# Sheet1.net
KiCad netlist of a schematic drawn in Altium Designer
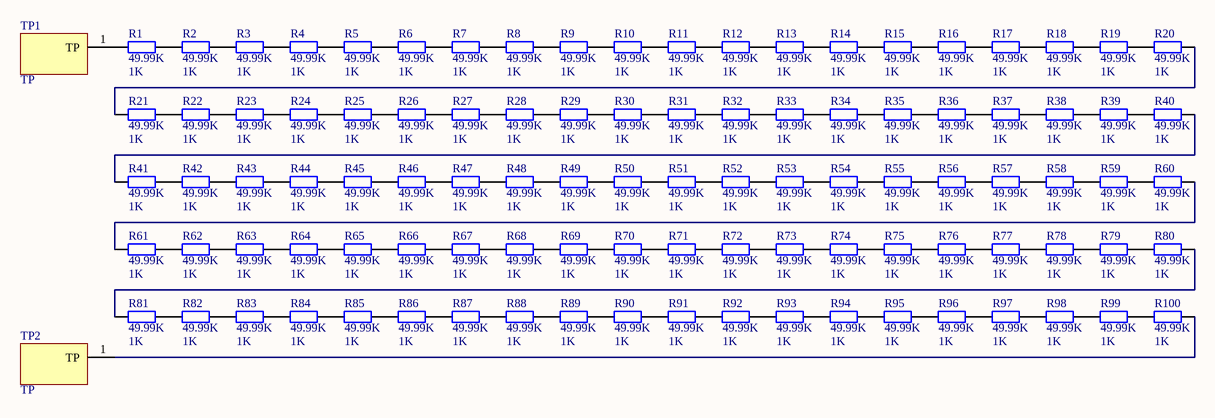
[diagram p0: Sheet1.SchDoc]

(export (version "E")
  (design (tool "Eeschema 10.0.6"))
  (components
    (comp (ref "R1")
      (value "49.99K")
      (footprint "AXIAL-0.4")
      (description "Resistor")
      (fields (field (name "ALTIUM_VALUE") "1K") (field (name "PUBLISHER") "Altium Limited"))
      (libsource (lib "Miscellaneous Devices") (part "Res2"))
    )
    (comp (ref "R2")
      (value "49.99K")
      (footprint "AXIAL-0.4")
      (description "Resistor")
      (fields (field (name "ALTIUM_VALUE") "1K") (field (name "PUBLISHER") "Altium Limited"))
      (libsource (lib "Miscellaneous Devices") (part "Res2"))
    )
    (comp (ref "R3")
      (value "49.99K")
      (footprint "AXIAL-0.4")
      (description "Resistor")
      (fields (field (name "ALTIUM_VALUE") "1K") (field (name "PUBLISHER") "Altium Limited"))
      (libsource (lib "Miscellaneous Devices") (part "Res2"))
    )
    (comp (ref "R4")
      (value "49.99K")
      (footprint "AXIAL-0.4")
      (description "Resistor")
      (fields (field (name "ALTIUM_VALUE") "1K") (field (name "PUBLISHER") "Altium Limited"))
      (libsource (lib "Miscellaneous Devices") (part "Res2"))
    )
    (comp (ref "R5")
      (value "49.99K")
      (footprint "AXIAL-0.4")
      (description "Resistor")
      (fields (field (name "ALTIUM_VALUE") "1K") (field (name "PUBLISHER") "Altium Limited"))
      (libsource (lib "Miscellaneous Devices") (part "Res2"))
    )
    (comp (ref "R6")
      (value "49.99K")
      (footprint "AXIAL-0.4")
      (description "Resistor")
      (fields (field (name "ALTIUM_VALUE") "1K") (field (name "PUBLISHER") "Altium Limited"))
      (libsource (lib "Miscellaneous Devices") (part "Res2"))
    )
    (comp (ref "R7")
      (value "49.99K")
      (footprint "AXIAL-0.4")
      (description "Resistor")
      (fields (field (name "ALTIUM_VALUE") "1K") (field (name "PUBLISHER") "Altium Limited"))
      (libsource (lib "Miscellaneous Devices") (part "Res2"))
    )
    (comp (ref "R8")
      (value "49.99K")
      (footprint "AXIAL-0.4")
      (description "Resistor")
      (fields (field (name "ALTIUM_VALUE") "1K") (field (name "PUBLISHER") "Altium Limited"))
      (libsource (lib "Miscellaneous Devices") (part "Res2"))
    )
    (comp (ref "R9")
      (value "49.99K")
      (footprint "AXIAL-0.4")
      (description "Resistor")
      (fields (field (name "ALTIUM_VALUE") "1K") (field (name "PUBLISHER") "Altium Limited"))
      (libsource (lib "Miscellaneous Devices") (part "Res2"))
    )
    (comp (ref "R10")
      (value "49.99K")
      (footprint "AXIAL-0.4")
      (description "Resistor")
      (fields (field (name "ALTIUM_VALUE") "1K") (field (name "PUBLISHER") "Altium Limited"))
      (libsource (lib "Miscellaneous Devices") (part "Res2"))
    )
    (comp (ref "R11")
      (value "49.99K")
      (footprint "AXIAL-0.4")
      (description "Resistor")
      (fields (field (name "ALTIUM_VALUE") "1K") (field (name "PUBLISHER") "Altium Limited"))
      (libsource (lib "Miscellaneous Devices") (part "Res2"))
    )
    (comp (ref "R12")
      (value "49.99K")
      (footprint "AXIAL-0.4")
      (description "Resistor")
      (fields (field (name "ALTIUM_VALUE") "1K") (field (name "PUBLISHER") "Altium Limited"))
      (libsource (lib "Miscellaneous Devices") (part "Res2"))
    )
    (comp (ref "R13")
      (value "49.99K")
      (footprint "AXIAL-0.4")
      (description "Resistor")
      (fields (field (name "ALTIUM_VALUE") "1K") (field (name "PUBLISHER") "Altium Limited"))
      (libsource (lib "Miscellaneous Devices") (part "Res2"))
    )
    (comp (ref "R14")
      (value "49.99K")
      (footprint "AXIAL-0.4")
      (description "Resistor")
      (fields (field (name "ALTIUM_VALUE") "1K") (field (name "PUBLISHER") "Altium Limited"))
      (libsource (lib "Miscellaneous Devices") (part "Res2"))
    )
    (comp (ref "R15")
      (value "49.99K")
      (footprint "AXIAL-0.4")
      (description "Resistor")
      (fields (field (name "ALTIUM_VALUE") "1K") (field (name "PUBLISHER") "Altium Limited"))
      (libsource (lib "Miscellaneous Devices") (part "Res2"))
    )
    (comp (ref "R16")
      (value "49.99K")
      (footprint "AXIAL-0.4")
      (description "Resistor")
      (fields (field (name "ALTIUM_VALUE") "1K") (field (name "PUBLISHER") "Altium Limited"))
      (libsource (lib "Miscellaneous Devices") (part "Res2"))
    )
    (comp (ref "R17")
      (value "49.99K")
      (footprint "AXIAL-0.4")
      (description "Resistor")
      (fields (field (name "ALTIUM_VALUE") "1K") (field (name "PUBLISHER") "Altium Limited"))
      (libsource (lib "Miscellaneous Devices") (part "Res2"))
    )
    (comp (ref "R18")
      (value "49.99K")
      (footprint "AXIAL-0.4")
      (description "Resistor")
      (fields (field (name "ALTIUM_VALUE") "1K") (field (name "PUBLISHER") "Altium Limited"))
      (libsource (lib "Miscellaneous Devices") (part "Res2"))
    )
    (comp (ref "R19")
      (value "49.99K")
      (footprint "AXIAL-0.4")
      (description "Resistor")
      (fields (field (name "ALTIUM_VALUE") "1K") (field (name "PUBLISHER") "Altium Limited"))
      (libsource (lib "Miscellaneous Devices") (part "Res2"))
    )
    (comp (ref "R20")
      (value "49.99K")
      (footprint "AXIAL-0.4")
      (description "Resistor")
      (fields (field (name "ALTIUM_VALUE") "1K") (field (name "PUBLISHER") "Altium Limited"))
      (libsource (lib "Miscellaneous Devices") (part "Res2"))
    )
    (comp (ref "R21")
      (value "49.99K")
      (footprint "AXIAL-0.4")
      (description "Resistor")
      (fields (field (name "ALTIUM_VALUE") "1K") (field (name "PUBLISHER") "Altium Limited"))
      (libsource (lib "Miscellaneous Devices") (part "Res2"))
    )
    (comp (ref "R22")
      (value "49.99K")
      (footprint "AXIAL-0.4")
      (description "Resistor")
      (fields (field (name "ALTIUM_VALUE") "1K") (field (name "PUBLISHER") "Altium Limited"))
      (libsource (lib "Miscellaneous Devices") (part "Res2"))
    )
    (comp (ref "R23")
      (value "49.99K")
      (footprint "AXIAL-0.4")
      (description "Resistor")
      (fields (field (name "ALTIUM_VALUE") "1K") (field (name "PUBLISHER") "Altium Limited"))
      (libsource (lib "Miscellaneous Devices") (part "Res2"))
    )
    (comp (ref "R24")
      (value "49.99K")
      (footprint "AXIAL-0.4")
      (description "Resistor")
      (fields (field (name "ALTIUM_VALUE") "1K") (field (name "PUBLISHER") "Altium Limited"))
      (libsource (lib "Miscellaneous Devices") (part "Res2"))
    )
    (comp (ref "R25")
      (value "49.99K")
      (footprint "AXIAL-0.4")
      (description "Resistor")
      (fields (field (name "ALTIUM_VALUE") "1K") (field (name "PUBLISHER") "Altium Limited"))
      (libsource (lib "Miscellaneous Devices") (part "Res2"))
    )
    (comp (ref "R26")
      (value "49.99K")
      (footprint "AXIAL-0.4")
      (description "Resistor")
      (fields (field (name "ALTIUM_VALUE") "1K") (field (name "PUBLISHER") "Altium Limited"))
      (libsource (lib "Miscellaneous Devices") (part "Res2"))
    )
    (comp (ref "R27")
      (value "49.99K")
      (footprint "AXIAL-0.4")
      (description "Resistor")
      (fields (field (name "ALTIUM_VALUE") "1K") (field (name "PUBLISHER") "Altium Limited"))
      (libsource (lib "Miscellaneous Devices") (part "Res2"))
    )
    (comp (ref "R28")
      (value "49.99K")
      (footprint "AXIAL-0.4")
      (description "Resistor")
      (fields (field (name "ALTIUM_VALUE") "1K") (field (name "PUBLISHER") "Altium Limited"))
      (libsource (lib "Miscellaneous Devices") (part "Res2"))
    )
    (comp (ref "R29")
      (value "49.99K")
      (footprint "AXIAL-0.4")
      (description "Resistor")
      (fields (field (name "ALTIUM_VALUE") "1K") (field (name "PUBLISHER") "Altium Limited"))
      (libsource (lib "Miscellaneous Devices") (part "Res2"))
    )
    (comp (ref "R30")
      (value "49.99K")
      (footprint "AXIAL-0.4")
      (description "Resistor")
      (fields (field (name "ALTIUM_VALUE") "1K") (field (name "PUBLISHER") "Altium Limited"))
      (libsource (lib "Miscellaneous Devices") (part "Res2"))
    )
    (comp (ref "R31")
      (value "49.99K")
      (footprint "AXIAL-0.4")
      (description "Resistor")
      (fields (field (name "ALTIUM_VALUE") "1K") (field (name "PUBLISHER") "Altium Limited"))
      (libsource (lib "Miscellaneous Devices") (part "Res2"))
    )
    (comp (ref "R32")
      (value "49.99K")
      (footprint "AXIAL-0.4")
      (description "Resistor")
      (fields (field (name "ALTIUM_VALUE") "1K") (field (name "PUBLISHER") "Altium Limited"))
      (libsource (lib "Miscellaneous Devices") (part "Res2"))
    )
    (comp (ref "R33")
      (value "49.99K")
      (footprint "AXIAL-0.4")
      (description "Resistor")
      (fields (field (name "ALTIUM_VALUE") "1K") (field (name "PUBLISHER") "Altium Limited"))
      (libsource (lib "Miscellaneous Devices") (part "Res2"))
    )
    (comp (ref "R34")
      (value "49.99K")
      (footprint "AXIAL-0.4")
      (description "Resistor")
      (fields (field (name "ALTIUM_VALUE") "1K") (field (name "PUBLISHER") "Altium Limited"))
      (libsource (lib "Miscellaneous Devices") (part "Res2"))
    )
    (comp (ref "R35")
      (value "49.99K")
      (footprint "AXIAL-0.4")
      (description "Resistor")
      (fields (field (name "ALTIUM_VALUE") "1K") (field (name "PUBLISHER") "Altium Limited"))
      (libsource (lib "Miscellaneous Devices") (part "Res2"))
    )
    (comp (ref "R36")
      (value "49.99K")
      (footprint "AXIAL-0.4")
      (description "Resistor")
      (fields (field (name "ALTIUM_VALUE") "1K") (field (name "PUBLISHER") "Altium Limited"))
      (libsource (lib "Miscellaneous Devices") (part "Res2"))
    )
    (comp (ref "R37")
      (value "49.99K")
      (footprint "AXIAL-0.4")
      (description "Resistor")
      (fields (field (name "ALTIUM_VALUE") "1K") (field (name "PUBLISHER") "Altium Limited"))
      (libsource (lib "Miscellaneous Devices") (part "Res2"))
    )
    (comp (ref "R38")
      (value "49.99K")
      (footprint "AXIAL-0.4")
      (description "Resistor")
      (fields (field (name "ALTIUM_VALUE") "1K") (field (name "PUBLISHER") "Altium Limited"))
      (libsource (lib "Miscellaneous Devices") (part "Res2"))
    )
    (comp (ref "R39")
      (value "49.99K")
      (footprint "AXIAL-0.4")
      (description "Resistor")
      (fields (field (name "ALTIUM_VALUE") "1K") (field (name "PUBLISHER") "Altium Limited"))
      (libsource (lib "Miscellaneous Devices") (part "Res2"))
    )
    (comp (ref "R40")
      (value "49.99K")
      (footprint "AXIAL-0.4")
      (description "Resistor")
      (fields (field (name "ALTIUM_VALUE") "1K") (field (name "PUBLISHER") "Altium Limited"))
      (libsource (lib "Miscellaneous Devices") (part "Res2"))
    )
    (comp (ref "R41")
      (value "49.99K")
      (footprint "AXIAL-0.4")
      (description "Resistor")
      (fields (field (name "ALTIUM_VALUE") "1K") (field (name "PUBLISHER") "Altium Limited"))
      (libsource (lib "Miscellaneous Devices") (part "Res2"))
    )
    (comp (ref "R42")
      (value "49.99K")
      (footprint "AXIAL-0.4")
      (description "Resistor")
      (fields (field (name "ALTIUM_VALUE") "1K") (field (name "PUBLISHER") "Altium Limited"))
      (libsource (lib "Miscellaneous Devices") (part "Res2"))
    )
    (comp (ref "R43")
      (value "49.99K")
      (footprint "AXIAL-0.4")
      (description "Resistor")
      (fields (field (name "ALTIUM_VALUE") "1K") (field (name "PUBLISHER") "Altium Limited"))
      (libsource (lib "Miscellaneous Devices") (part "Res2"))
    )
    (comp (ref "R44")
      (value "49.99K")
      (footprint "AXIAL-0.4")
      (description "Resistor")
      (fields (field (name "ALTIUM_VALUE") "1K") (field (name "PUBLISHER") "Altium Limited"))
      (libsource (lib "Miscellaneous Devices") (part "Res2"))
    )
    (comp (ref "R45")
      (value "49.99K")
      (footprint "AXIAL-0.4")
      (description "Resistor")
      (fields (field (name "ALTIUM_VALUE") "1K") (field (name "PUBLISHER") "Altium Limited"))
      (libsource (lib "Miscellaneous Devices") (part "Res2"))
    )
    (comp (ref "R46")
      (value "49.99K")
      (footprint "AXIAL-0.4")
      (description "Resistor")
      (fields (field (name "ALTIUM_VALUE") "1K") (field (name "PUBLISHER") "Altium Limited"))
      (libsource (lib "Miscellaneous Devices") (part "Res2"))
    )
    (comp (ref "R47")
      (value "49.99K")
      (footprint "AXIAL-0.4")
      (description "Resistor")
      (fields (field (name "ALTIUM_VALUE") "1K") (field (name "PUBLISHER") "Altium Limited"))
      (libsource (lib "Miscellaneous Devices") (part "Res2"))
    )
    (comp (ref "R48")
      (value "49.99K")
      (footprint "AXIAL-0.4")
      (description "Resistor")
      (fields (field (name "ALTIUM_VALUE") "1K") (field (name "PUBLISHER") "Altium Limited"))
      (libsource (lib "Miscellaneous Devices") (part "Res2"))
    )
    (comp (ref "R49")
      (value "49.99K")
      (footprint "AXIAL-0.4")
      (description "Resistor")
      (fields (field (name "ALTIUM_VALUE") "1K") (field (name "PUBLISHER") "Altium Limited"))
      (libsource (lib "Miscellaneous Devices") (part "Res2"))
    )
    (comp (ref "R50")
      (value "49.99K")
      (footprint "AXIAL-0.4")
      (description "Resistor")
      (fields (field (name "ALTIUM_VALUE") "1K") (field (name "PUBLISHER") "Altium Limited"))
      (libsource (lib "Miscellaneous Devices") (part "Res2"))
    )
    (comp (ref "R51")
      (value "49.99K")
      (footprint "AXIAL-0.4")
      (description "Resistor")
      (fields (field (name "ALTIUM_VALUE") "1K") (field (name "PUBLISHER") "Altium Limited"))
      (libsource (lib "Miscellaneous Devices") (part "Res2"))
    )
    (comp (ref "R52")
      (value "49.99K")
      (footprint "AXIAL-0.4")
      (description "Resistor")
      (fields (field (name "ALTIUM_VALUE") "1K") (field (name "PUBLISHER") "Altium Limited"))
      (libsource (lib "Miscellaneous Devices") (part "Res2"))
    )
    (comp (ref "R53")
      (value "49.99K")
      (footprint "AXIAL-0.4")
      (description "Resistor")
      (fields (field (name "ALTIUM_VALUE") "1K") (field (name "PUBLISHER") "Altium Limited"))
      (libsource (lib "Miscellaneous Devices") (part "Res2"))
    )
    (comp (ref "R54")
      (value "49.99K")
      (footprint "AXIAL-0.4")
      (description "Resistor")
      (fields (field (name "ALTIUM_VALUE") "1K") (field (name "PUBLISHER") "Altium Limited"))
      (libsource (lib "Miscellaneous Devices") (part "Res2"))
    )
    (comp (ref "R55")
      (value "49.99K")
      (footprint "AXIAL-0.4")
      (description "Resistor")
      (fields (field (name "ALTIUM_VALUE") "1K") (field (name "PUBLISHER") "Altium Limited"))
      (libsource (lib "Miscellaneous Devices") (part "Res2"))
    )
    (comp (ref "R56")
      (value "49.99K")
      (footprint "AXIAL-0.4")
      (description "Resistor")
      (fields (field (name "ALTIUM_VALUE") "1K") (field (name "PUBLISHER") "Altium Limited"))
      (libsource (lib "Miscellaneous Devices") (part "Res2"))
    )
    (comp (ref "R57")
      (value "49.99K")
      (footprint "AXIAL-0.4")
      (description "Resistor")
      (fields (field (name "ALTIUM_VALUE") "1K") (field (name "PUBLISHER") "Altium Limited"))
      (libsource (lib "Miscellaneous Devices") (part "Res2"))
    )
    (comp (ref "R58")
      (value "49.99K")
      (footprint "AXIAL-0.4")
      (description "Resistor")
      (fields (field (name "ALTIUM_VALUE") "1K") (field (name "PUBLISHER") "Altium Limited"))
      (libsource (lib "Miscellaneous Devices") (part "Res2"))
    )
    (comp (ref "R59")
      (value "49.99K")
      (footprint "AXIAL-0.4")
      (description "Resistor")
      (fields (field (name "ALTIUM_VALUE") "1K") (field (name "PUBLISHER") "Altium Limited"))
      (libsource (lib "Miscellaneous Devices") (part "Res2"))
    )
    (comp (ref "R60")
      (value "49.99K")
      (footprint "AXIAL-0.4")
      (description "Resistor")
      (fields (field (name "ALTIUM_VALUE") "1K") (field (name "PUBLISHER") "Altium Limited"))
      (libsource (lib "Miscellaneous Devices") (part "Res2"))
    )
    (comp (ref "R61")
      (value "49.99K")
      (footprint "AXIAL-0.4")
      (description "Resistor")
      (fields (field (name "ALTIUM_VALUE") "1K") (field (name "PUBLISHER") "Altium Limited"))
      (libsource (lib "Miscellaneous Devices") (part "Res2"))
    )
    (comp (ref "R62")
      (value "49.99K")
      (footprint "AXIAL-0.4")
      (description "Resistor")
      (fields (field (name "ALTIUM_VALUE") "1K") (field (name "PUBLISHER") "Altium Limited"))
      (libsource (lib "Miscellaneous Devices") (part "Res2"))
    )
    (comp (ref "R63")
      (value "49.99K")
      (footprint "AXIAL-0.4")
      (description "Resistor")
      (fields (field (name "ALTIUM_VALUE") "1K") (field (name "PUBLISHER") "Altium Limited"))
      (libsource (lib "Miscellaneous Devices") (part "Res2"))
    )
    (comp (ref "R64")
      (value "49.99K")
      (footprint "AXIAL-0.4")
      (description "Resistor")
      (fields (field (name "ALTIUM_VALUE") "1K") (field (name "PUBLISHER") "Altium Limited"))
      (libsource (lib "Miscellaneous Devices") (part "Res2"))
    )
    (comp (ref "R65")
      (value "49.99K")
      (footprint "AXIAL-0.4")
      (description "Resistor")
      (fields (field (name "ALTIUM_VALUE") "1K") (field (name "PUBLISHER") "Altium Limited"))
      (libsource (lib "Miscellaneous Devices") (part "Res2"))
    )
    (comp (ref "R66")
      (value "49.99K")
      (footprint "AXIAL-0.4")
      (description "Resistor")
      (fields (field (name "ALTIUM_VALUE") "1K") (field (name "PUBLISHER") "Altium Limited"))
      (libsource (lib "Miscellaneous Devices") (part "Res2"))
    )
    (comp (ref "R67")
      (value "49.99K")
      (footprint "AXIAL-0.4")
      (description "Resistor")
      (fields (field (name "ALTIUM_VALUE") "1K") (field (name "PUBLISHER") "Altium Limited"))
      (libsource (lib "Miscellaneous Devices") (part "Res2"))
    )
    (comp (ref "R68")
      (value "49.99K")
      (footprint "AXIAL-0.4")
      (description "Resistor")
      (fields (field (name "ALTIUM_VALUE") "1K") (field (name "PUBLISHER") "Altium Limited"))
      (libsource (lib "Miscellaneous Devices") (part "Res2"))
    )
    (comp (ref "R69")
      (value "49.99K")
      (footprint "AXIAL-0.4")
      (description "Resistor")
      (fields (field (name "ALTIUM_VALUE") "1K") (field (name "PUBLISHER") "Altium Limited"))
      (libsource (lib "Miscellaneous Devices") (part "Res2"))
    )
    (comp (ref "R70")
      (value "49.99K")
      (footprint "AXIAL-0.4")
      (description "Resistor")
      (fields (field (name "ALTIUM_VALUE") "1K") (field (name "PUBLISHER") "Altium Limited"))
      (libsource (lib "Miscellaneous Devices") (part "Res2"))
    )
    (comp (ref "R71")
      (value "49.99K")
      (footprint "AXIAL-0.4")
      (description "Resistor")
      (fields (field (name "ALTIUM_VALUE") "1K") (field (name "PUBLISHER") "Altium Limited"))
      (libsource (lib "Miscellaneous Devices") (part "Res2"))
    )
    (comp (ref "R72")
      (value "49.99K")
      (footprint "AXIAL-0.4")
      (description "Resistor")
      (fields (field (name "ALTIUM_VALUE") "1K") (field (name "PUBLISHER") "Altium Limited"))
      (libsource (lib "Miscellaneous Devices") (part "Res2"))
    )
    (comp (ref "R73")
      (value "49.99K")
      (footprint "AXIAL-0.4")
      (description "Resistor")
      (fields (field (name "ALTIUM_VALUE") "1K") (field (name "PUBLISHER") "Altium Limited"))
      (libsource (lib "Miscellaneous Devices") (part "Res2"))
    )
    (comp (ref "R74")
      (value "49.99K")
      (footprint "AXIAL-0.4")
      (description "Resistor")
      (fields (field (name "ALTIUM_VALUE") "1K") (field (name "PUBLISHER") "Altium Limited"))
      (libsource (lib "Miscellaneous Devices") (part "Res2"))
    )
    (comp (ref "R75")
      (value "49.99K")
      (footprint "AXIAL-0.4")
      (description "Resistor")
      (fields (field (name "ALTIUM_VALUE") "1K") (field (name "PUBLISHER") "Altium Limited"))
      (libsource (lib "Miscellaneous Devices") (part "Res2"))
    )
    (comp (ref "R76")
      (value "49.99K")
      (footprint "AXIAL-0.4")
      (description "Resistor")
      (fields (field (name "ALTIUM_VALUE") "1K") (field (name "PUBLISHER") "Altium Limited"))
      (libsource (lib "Miscellaneous Devices") (part "Res2"))
    )
    (comp (ref "R77")
      (value "49.99K")
      (footprint "AXIAL-0.4")
      (description "Resistor")
      (fields (field (name "ALTIUM_VALUE") "1K") (field (name "PUBLISHER") "Altium Limited"))
      (libsource (lib "Miscellaneous Devices") (part "Res2"))
    )
    (comp (ref "R78")
      (value "49.99K")
      (footprint "AXIAL-0.4")
      (description "Resistor")
      (fields (field (name "ALTIUM_VALUE") "1K") (field (name "PUBLISHER") "Altium Limited"))
      (libsource (lib "Miscellaneous Devices") (part "Res2"))
    )
    (comp (ref "R79")
      (value "49.99K")
      (footprint "AXIAL-0.4")
      (description "Resistor")
      (fields (field (name "ALTIUM_VALUE") "1K") (field (name "PUBLISHER") "Altium Limited"))
      (libsource (lib "Miscellaneous Devices") (part "Res2"))
    )
    (comp (ref "R80")
      (value "49.99K")
      (footprint "AXIAL-0.4")
      (description "Resistor")
      (fields (field (name "ALTIUM_VALUE") "1K") (field (name "PUBLISHER") "Altium Limited"))
      (libsource (lib "Miscellaneous Devices") (part "Res2"))
    )
    (comp (ref "R81")
      (value "49.99K")
      (footprint "AXIAL-0.4")
      (description "Resistor")
      (fields (field (name "ALTIUM_VALUE") "1K") (field (name "PUBLISHER") "Altium Limited"))
      (libsource (lib "Miscellaneous Devices") (part "Res2"))
    )
    (comp (ref "R82")
      (value "49.99K")
      (footprint "AXIAL-0.4")
      (description "Resistor")
      (fields (field (name "ALTIUM_VALUE") "1K") (field (name "PUBLISHER") "Altium Limited"))
      (libsource (lib "Miscellaneous Devices") (part "Res2"))
    )
    (comp (ref "R83")
      (value "49.99K")
      (footprint "AXIAL-0.4")
      (description "Resistor")
      (fields (field (name "ALTIUM_VALUE") "1K") (field (name "PUBLISHER") "Altium Limited"))
      (libsource (lib "Miscellaneous Devices") (part "Res2"))
    )
    (comp (ref "R84")
      (value "49.99K")
      (footprint "AXIAL-0.4")
      (description "Resistor")
      (fields (field (name "ALTIUM_VALUE") "1K") (field (name "PUBLISHER") "Altium Limited"))
      (libsource (lib "Miscellaneous Devices") (part "Res2"))
    )
    (comp (ref "R85")
      (value "49.99K")
      (footprint "AXIAL-0.4")
      (description "Resistor")
      (fields (field (name "ALTIUM_VALUE") "1K") (field (name "PUBLISHER") "Altium Limited"))
      (libsource (lib "Miscellaneous Devices") (part "Res2"))
    )
    (comp (ref "R86")
      (value "49.99K")
      (footprint "AXIAL-0.4")
      (description "Resistor")
      (fields (field (name "ALTIUM_VALUE") "1K") (field (name "PUBLISHER") "Altium Limited"))
      (libsource (lib "Miscellaneous Devices") (part "Res2"))
    )
    (comp (ref "R87")
      (value "49.99K")
      (footprint "AXIAL-0.4")
      (description "Resistor")
      (fields (field (name "ALTIUM_VALUE") "1K") (field (name "PUBLISHER") "Altium Limited"))
      (libsource (lib "Miscellaneous Devices") (part "Res2"))
    )
    (comp (ref "R88")
      (value "49.99K")
      (footprint "AXIAL-0.4")
      (description "Resistor")
      (fields (field (name "ALTIUM_VALUE") "1K") (field (name "PUBLISHER") "Altium Limited"))
      (libsource (lib "Miscellaneous Devices") (part "Res2"))
    )
    (comp (ref "R89")
      (value "49.99K")
      (footprint "AXIAL-0.4")
      (description "Resistor")
      (fields (field (name "ALTIUM_VALUE") "1K") (field (name "PUBLISHER") "Altium Limited"))
      (libsource (lib "Miscellaneous Devices") (part "Res2"))
    )
    (comp (ref "R90")
      (value "49.99K")
      (footprint "AXIAL-0.4")
      (description "Resistor")
      (fields (field (name "ALTIUM_VALUE") "1K") (field (name "PUBLISHER") "Altium Limited"))
      (libsource (lib "Miscellaneous Devices") (part "Res2"))
    )
    (comp (ref "R91")
      (value "49.99K")
      (footprint "AXIAL-0.4")
      (description "Resistor")
      (fields (field (name "ALTIUM_VALUE") "1K") (field (name "PUBLISHER") "Altium Limited"))
      (libsource (lib "Miscellaneous Devices") (part "Res2"))
    )
    (comp (ref "R92")
      (value "49.99K")
      (footprint "AXIAL-0.4")
      (description "Resistor")
      (fields (field (name "ALTIUM_VALUE") "1K") (field (name "PUBLISHER") "Altium Limited"))
      (libsource (lib "Miscellaneous Devices") (part "Res2"))
    )
    (comp (ref "R93")
      (value "49.99K")
      (footprint "AXIAL-0.4")
      (description "Resistor")
      (fields (field (name "ALTIUM_VALUE") "1K") (field (name "PUBLISHER") "Altium Limited"))
      (libsource (lib "Miscellaneous Devices") (part "Res2"))
    )
    (comp (ref "R94")
      (value "49.99K")
      (footprint "AXIAL-0.4")
      (description "Resistor")
      (fields (field (name "ALTIUM_VALUE") "1K") (field (name "PUBLISHER") "Altium Limited"))
      (libsource (lib "Miscellaneous Devices") (part "Res2"))
    )
    (comp (ref "R95")
      (value "49.99K")
      (footprint "AXIAL-0.4")
      (description "Resistor")
      (fields (field (name "ALTIUM_VALUE") "1K") (field (name "PUBLISHER") "Altium Limited"))
      (libsource (lib "Miscellaneous Devices") (part "Res2"))
    )
    (comp (ref "R96")
      (value "49.99K")
      (footprint "AXIAL-0.4")
      (description "Resistor")
      (fields (field (name "ALTIUM_VALUE") "1K") (field (name "PUBLISHER") "Altium Limited"))
      (libsource (lib "Miscellaneous Devices") (part "Res2"))
    )
    (comp (ref "R97")
      (value "49.99K")
      (footprint "AXIAL-0.4")
      (description "Resistor")
      (fields (field (name "ALTIUM_VALUE") "1K") (field (name "PUBLISHER") "Altium Limited"))
      (libsource (lib "Miscellaneous Devices") (part "Res2"))
    )
    (comp (ref "R98")
      (value "49.99K")
      (footprint "AXIAL-0.4")
      (description "Resistor")
      (fields (field (name "ALTIUM_VALUE") "1K") (field (name "PUBLISHER") "Altium Limited"))
      (libsource (lib "Miscellaneous Devices") (part "Res2"))
    )
    (comp (ref "R99")
      (value "49.99K")
      (footprint "AXIAL-0.4")
      (description "Resistor")
      (fields (field (name "ALTIUM_VALUE") "1K") (field (name "PUBLISHER") "Altium Limited"))
      (libsource (lib "Miscellaneous Devices") (part "Res2"))
    )
    (comp (ref "R100")
      (value "49.99K")
      (footprint "AXIAL-0.4")
      (description "Resistor")
      (fields (field (name "ALTIUM_VALUE") "1K") (field (name "PUBLISHER") "Altium Limited"))
      (libsource (lib "Miscellaneous Devices") (part "Res2"))
    )
    (comp (ref "TP1") (value "TP") (footprint "TP") (libsource (lib "Schlib1") (part "TP")))
    (comp (ref "TP2") (value "TP") (footprint "TP") (libsource (lib "Schlib1") (part "TP")))
  )
  (nets
    (net (code "1") (name "Net-(R1-Pad1)") (class "Default")
      (node (ref "R1") (pin "1") (pinfunction "1_1") (pintype "passive"))
      (node (ref "R2") (pin "2") (pinfunction "2_2") (pintype "passive"))
    )
    (net (code "2") (name "Net-(R2-Pad1)") (class "Default")
      (node (ref "R2") (pin "1") (pinfunction "1_1") (pintype "passive"))
      (node (ref "R3") (pin "2") (pinfunction "2_2") (pintype "passive"))
    )
    (net (code "3") (name "Net-(R3-Pad1)") (class "Default")
      (node (ref "R3") (pin "1") (pinfunction "1_1") (pintype "passive"))
      (node (ref "R4") (pin "2") (pinfunction "2_2") (pintype "passive"))
    )
    (net (code "4") (name "Net-(R4-Pad1)") (class "Default")
      (node (ref "R4") (pin "1") (pinfunction "1_1") (pintype "passive"))
      (node (ref "R5") (pin "2") (pinfunction "2_2") (pintype "passive"))
    )
    (net (code "5") (name "Net-(R5-Pad1)") (class "Default")
      (node (ref "R5") (pin "1") (pinfunction "1_1") (pintype "passive"))
      (node (ref "R6") (pin "2") (pinfunction "2_2") (pintype "passive"))
    )
    (net (code "6") (name "Net-(R6-Pad1)") (class "Default")
      (node (ref "R6") (pin "1") (pinfunction "1_1") (pintype "passive"))
      (node (ref "R7") (pin "2") (pinfunction "2_2") (pintype "passive"))
    )
    (net (code "7") (name "Net-(R7-Pad1)") (class "Default")
      (node (ref "R7") (pin "1") (pinfunction "1_1") (pintype "passive"))
      (node (ref "R8") (pin "2") (pinfunction "2_2") (pintype "passive"))
    )
    (net (code "8") (name "Net-(R8-Pad1)") (class "Default")
      (node (ref "R8") (pin "1") (pinfunction "1_1") (pintype "passive"))
      (node (ref "R9") (pin "2") (pinfunction "2_2") (pintype "passive"))
    )
    (net (code "9") (name "Net-(R10-Pad1)") (class "Default")
      (node (ref "R10") (pin "1") (pinfunction "1_1") (pintype "passive"))
      (node (ref "R11") (pin "2") (pinfunction "2_2") (pintype "passive"))
    )
    (net (code "10") (name "Net-(R10-Pad2)") (class "Default")
      (node (ref "R10") (pin "2") (pinfunction "2_2") (pintype "passive"))
      (node (ref "R9") (pin "1") (pinfunction "1_1") (pintype "passive"))
    )
    (net (code "11") (name "Net-(R11-Pad1)") (class "Default")
      (node (ref "R11") (pin "1") (pinfunction "1_1") (pintype "passive"))
      (node (ref "R12") (pin "2") (pinfunction "2_2") (pintype "passive"))
    )
    (net (code "12") (name "Net-(R12-Pad1)") (class "Default")
      (node (ref "R12") (pin "1") (pinfunction "1_1") (pintype "passive"))
      (node (ref "R13") (pin "2") (pinfunction "2_2") (pintype "passive"))
    )
    (net (code "13") (name "Net-(R13-Pad1)") (class "Default")
      (node (ref "R13") (pin "1") (pinfunction "1_1") (pintype "passive"))
      (node (ref "R14") (pin "2") (pinfunction "2_2") (pintype "passive"))
    )
    (net (code "14") (name "Net-(R14-Pad1)") (class "Default")
      (node (ref "R14") (pin "1") (pinfunction "1_1") (pintype "passive"))
      (node (ref "R15") (pin "2") (pinfunction "2_2") (pintype "passive"))
    )
    (net (code "15") (name "Net-(R15-Pad1)") (class "Default")
      (node (ref "R15") (pin "1") (pinfunction "1_1") (pintype "passive"))
      (node (ref "R16") (pin "2") (pinfunction "2_2") (pintype "passive"))
    )
    (net (code "16") (name "Net-(R16-Pad1)") (class "Default")
      (node (ref "R16") (pin "1") (pinfunction "1_1") (pintype "passive"))
      (node (ref "R17") (pin "2") (pinfunction "2_2") (pintype "passive"))
    )
    (net (code "17") (name "Net-(R17-Pad1)") (class "Default")
      (node (ref "R17") (pin "1") (pinfunction "1_1") (pintype "passive"))
      (node (ref "R18") (pin "2") (pinfunction "2_2") (pintype "passive"))
    )
    (net (code "18") (name "Net-(R18-Pad1)") (class "Default")
      (node (ref "R18") (pin "1") (pinfunction "1_1") (pintype "passive"))
      (node (ref "R19") (pin "2") (pinfunction "2_2") (pintype "passive"))
    )
    (net (code "19") (name "Net-(R19-Pad1)") (class "Default")
      (node (ref "R19") (pin "1") (pinfunction "1_1") (pintype "passive"))
      (node (ref "R20") (pin "2") (pinfunction "2_2") (pintype "passive"))
    )
    (net (code "20") (name "Net-(R20-Pad1)") (class "Default")
      (node (ref "R20") (pin "1") (pinfunction "1_1") (pintype "passive"))
      (node (ref "R21") (pin "2") (pinfunction "2_2") (pintype "passive"))
    )
    (net (code "21") (name "Net-(R21-Pad1)") (class "Default")
      (node (ref "R21") (pin "1") (pinfunction "1_1") (pintype "passive"))
      (node (ref "R22") (pin "2") (pinfunction "2_2") (pintype "passive"))
    )
    (net (code "22") (name "Net-(R22-Pad1)") (class "Default")
      (node (ref "R22") (pin "1") (pinfunction "1_1") (pintype "passive"))
      (node (ref "R23") (pin "2") (pinfunction "2_2") (pintype "passive"))
    )
    (net (code "23") (name "Net-(R23-Pad1)") (class "Default")
      (node (ref "R23") (pin "1") (pinfunction "1_1") (pintype "passive"))
      (node (ref "R24") (pin "2") (pinfunction "2_2") (pintype "passive"))
    )
    (net (code "24") (name "Net-(R24-Pad1)") (class "Default")
      (node (ref "R24") (pin "1") (pinfunction "1_1") (pintype "passive"))
      (node (ref "R25") (pin "2") (pinfunction "2_2") (pintype "passive"))
    )
    (net (code "25") (name "Net-(R25-Pad1)") (class "Default")
      (node (ref "R25") (pin "1") (pinfunction "1_1") (pintype "passive"))
      (node (ref "R26") (pin "2") (pinfunction "2_2") (pintype "passive"))
    )
    (net (code "26") (name "Net-(R26-Pad1)") (class "Default")
      (node (ref "R26") (pin "1") (pinfunction "1_1") (pintype "passive"))
      (node (ref "R27") (pin "2") (pinfunction "2_2") (pintype "passive"))
    )
    (net (code "27") (name "Net-(R27-Pad1)") (class "Default")
      (node (ref "R27") (pin "1") (pinfunction "1_1") (pintype "passive"))
      (node (ref "R28") (pin "2") (pinfunction "2_2") (pintype "passive"))
    )
    (net (code "28") (name "Net-(R28-Pad1)") (class "Default")
      (node (ref "R28") (pin "1") (pinfunction "1_1") (pintype "passive"))
      (node (ref "R29") (pin "2") (pinfunction "2_2") (pintype "passive"))
    )
    (net (code "29") (name "Net-(R29-Pad1)") (class "Default")
      (node (ref "R29") (pin "1") (pinfunction "1_1") (pintype "passive"))
      (node (ref "R30") (pin "2") (pinfunction "2_2") (pintype "passive"))
    )
    (net (code "30") (name "Net-(R30-Pad1)") (class "Default")
      (node (ref "R30") (pin "1") (pinfunction "1_1") (pintype "passive"))
      (node (ref "R31") (pin "2") (pinfunction "2_2") (pintype "passive"))
    )
    (net (code "31") (name "Net-(R31-Pad1)") (class "Default")
      (node (ref "R31") (pin "1") (pinfunction "1_1") (pintype "passive"))
      (node (ref "R32") (pin "2") (pinfunction "2_2") (pintype "passive"))
    )
    (net (code "32") (name "Net-(R32-Pad1)") (class "Default")
      (node (ref "R32") (pin "1") (pinfunction "1_1") (pintype "passive"))
      (node (ref "R33") (pin "2") (pinfunction "2_2") (pintype "passive"))
    )
    (net (code "33") (name "Net-(R33-Pad1)") (class "Default")
      (node (ref "R33") (pin "1") (pinfunction "1_1") (pintype "passive"))
      (node (ref "R34") (pin "2") (pinfunction "2_2") (pintype "passive"))
    )
    (net (code "34") (name "Net-(R34-Pad1)") (class "Default")
      (node (ref "R34") (pin "1") (pinfunction "1_1") (pintype "passive"))
      (node (ref "R35") (pin "2") (pinfunction "2_2") (pintype "passive"))
    )
    (net (code "35") (name "Net-(R35-Pad1)") (class "Default")
      (node (ref "R35") (pin "1") (pinfunction "1_1") (pintype "passive"))
      (node (ref "R36") (pin "2") (pinfunction "2_2") (pintype "passive"))
    )
    (net (code "36") (name "Net-(R36-Pad1)") (class "Default")
      (node (ref "R36") (pin "1") (pinfunction "1_1") (pintype "passive"))
      (node (ref "R37") (pin "2") (pinfunction "2_2") (pintype "passive"))
    )
    (net (code "37") (name "Net-(R37-Pad1)") (class "Default")
      (node (ref "R37") (pin "1") (pinfunction "1_1") (pintype "passive"))
      (node (ref "R38") (pin "2") (pinfunction "2_2") (pintype "passive"))
    )
    (net (code "38") (name "Net-(R38-Pad1)") (class "Default")
      (node (ref "R38") (pin "1") (pinfunction "1_1") (pintype "passive"))
      (node (ref "R39") (pin "2") (pinfunction "2_2") (pintype "passive"))
    )
    (net (code "39") (name "Net-(R39-Pad1)") (class "Default")
      (node (ref "R39") (pin "1") (pinfunction "1_1") (pintype "passive"))
      (node (ref "R40") (pin "2") (pinfunction "2_2") (pintype "passive"))
    )
    (net (code "40") (name "Net-(R40-Pad1)") (class "Default")
      (node (ref "R40") (pin "1") (pinfunction "1_1") (pintype "passive"))
      (node (ref "R41") (pin "2") (pinfunction "2_2") (pintype "passive"))
    )
    (net (code "41") (name "Net-(R41-Pad1)") (class "Default")
      (node (ref "R41") (pin "1") (pinfunction "1_1") (pintype "passive"))
      (node (ref "R42") (pin "2") (pinfunction "2_2") (pintype "passive"))
    )
    (net (code "42") (name "Net-(R42-Pad1)") (class "Default")
      (node (ref "R42") (pin "1") (pinfunction "1_1") (pintype "passive"))
      (node (ref "R43") (pin "2") (pinfunction "2_2") (pintype "passive"))
    )
    (net (code "43") (name "Net-(R43-Pad1)") (class "Default")
      (node (ref "R43") (pin "1") (pinfunction "1_1") (pintype "passive"))
      (node (ref "R44") (pin "2") (pinfunction "2_2") (pintype "passive"))
    )
    (net (code "44") (name "Net-(R44-Pad1)") (class "Default")
      (node (ref "R44") (pin "1") (pinfunction "1_1") (pintype "passive"))
      (node (ref "R45") (pin "2") (pinfunction "2_2") (pintype "passive"))
    )
    (net (code "45") (name "Net-(R45-Pad1)") (class "Default")
      (node (ref "R45") (pin "1") (pinfunction "1_1") (pintype "passive"))
      (node (ref "R46") (pin "2") (pinfunction "2_2") (pintype "passive"))
    )
    (net (code "46") (name "Net-(R46-Pad1)") (class "Default")
      (node (ref "R46") (pin "1") (pinfunction "1_1") (pintype "passive"))
      (node (ref "R47") (pin "2") (pinfunction "2_2") (pintype "passive"))
    )
    (net (code "47") (name "Net-(R47-Pad1)") (class "Default")
      (node (ref "R47") (pin "1") (pinfunction "1_1") (pintype "passive"))
      (node (ref "R48") (pin "2") (pinfunction "2_2") (pintype "passive"))
    )
    (net (code "48") (name "Net-(R48-Pad1)") (class "Default")
      (node (ref "R48") (pin "1") (pinfunction "1_1") (pintype "passive"))
      (node (ref "R49") (pin "2") (pinfunction "2_2") (pintype "passive"))
    )
    (net (code "49") (name "Net-(R49-Pad1)") (class "Default")
      (node (ref "R49") (pin "1") (pinfunction "1_1") (pintype "passive"))
      (node (ref "R50") (pin "2") (pinfunction "2_2") (pintype "passive"))
    )
    (net (code "50") (name "Net-(R50-Pad1)") (class "Default")
      (node (ref "R50") (pin "1") (pinfunction "1_1") (pintype "passive"))
      (node (ref "R51") (pin "2") (pinfunction "2_2") (pintype "passive"))
    )
    (net (code "51") (name "Net-(R51-Pad1)") (class "Default")
      (node (ref "R51") (pin "1") (pinfunction "1_1") (pintype "passive"))
      (node (ref "R52") (pin "2") (pinfunction "2_2") (pintype "passive"))
    )
    (net (code "52") (name "Net-(R52-Pad1)") (class "Default")
      (node (ref "R52") (pin "1") (pinfunction "1_1") (pintype "passive"))
      (node (ref "R53") (pin "2") (pinfunction "2_2") (pintype "passive"))
    )
    (net (code "53") (name "Net-(R53-Pad1)") (class "Default")
      (node (ref "R53") (pin "1") (pinfunction "1_1") (pintype "passive"))
      (node (ref "R54") (pin "2") (pinfunction "2_2") (pintype "passive"))
    )
    (net (code "54") (name "Net-(R54-Pad1)") (class "Default")
      (node (ref "R54") (pin "1") (pinfunction "1_1") (pintype "passive"))
      (node (ref "R55") (pin "2") (pinfunction "2_2") (pintype "passive"))
    )
    (net (code "55") (name "Net-(R55-Pad1)") (class "Default")
      (node (ref "R55") (pin "1") (pinfunction "1_1") (pintype "passive"))
      (node (ref "R56") (pin "2") (pinfunction "2_2") (pintype "passive"))
    )
    (net (code "56") (name "Net-(R56-Pad1)") (class "Default")
      (node (ref "R56") (pin "1") (pinfunction "1_1") (pintype "passive"))
      (node (ref "R57") (pin "2") (pinfunction "2_2") (pintype "passive"))
    )
    (net (code "57") (name "Net-(R57-Pad1)") (class "Default")
      (node (ref "R57") (pin "1") (pinfunction "1_1") (pintype "passive"))
      (node (ref "R58") (pin "2") (pinfunction "2_2") (pintype "passive"))
    )
    (net (code "58") (name "Net-(R58-Pad1)") (class "Default")
      (node (ref "R58") (pin "1") (pinfunction "1_1") (pintype "passive"))
      (node (ref "R59") (pin "2") (pinfunction "2_2") (pintype "passive"))
    )
    (net (code "59") (name "Net-(R59-Pad1)") (class "Default")
      (node (ref "R59") (pin "1") (pinfunction "1_1") (pintype "passive"))
      (node (ref "R60") (pin "2") (pinfunction "2_2") (pintype "passive"))
    )
    (net (code "60") (name "Net-(R60-Pad1)") (class "Default")
      (node (ref "R60") (pin "1") (pinfunction "1_1") (pintype "passive"))
      (node (ref "R61") (pin "2") (pinfunction "2_2") (pintype "passive"))
    )
    (net (code "61") (name "Net-(R61-Pad1)") (class "Default")
      (node (ref "R61") (pin "1") (pinfunction "1_1") (pintype "passive"))
      (node (ref "R62") (pin "2") (pinfunction "2_2") (pintype "passive"))
    )
    (net (code "62") (name "Net-(R62-Pad1)") (class "Default")
      (node (ref "R62") (pin "1") (pinfunction "1_1") (pintype "passive"))
      (node (ref "R63") (pin "2") (pinfunction "2_2") (pintype "passive"))
    )
    (net (code "63") (name "Net-(R63-Pad1)") (class "Default")
      (node (ref "R63") (pin "1") (pinfunction "1_1") (pintype "passive"))
      (node (ref "R64") (pin "2") (pinfunction "2_2") (pintype "passive"))
    )
    (net (code "64") (name "Net-(R64-Pad1)") (class "Default")
      (node (ref "R64") (pin "1") (pinfunction "1_1") (pintype "passive"))
      (node (ref "R65") (pin "2") (pinfunction "2_2") (pintype "passive"))
    )
    (net (code "65") (name "Net-(R65-Pad1)") (class "Default")
      (node (ref "R65") (pin "1") (pinfunction "1_1") (pintype "passive"))
      (node (ref "R66") (pin "2") (pinfunction "2_2") (pintype "passive"))
    )
    (net (code "66") (name "Net-(R66-Pad1)") (class "Default")
      (node (ref "R66") (pin "1") (pinfunction "1_1") (pintype "passive"))
      (node (ref "R67") (pin "2") (pinfunction "2_2") (pintype "passive"))
    )
    (net (code "67") (name "Net-(R67-Pad1)") (class "Default")
      (node (ref "R67") (pin "1") (pinfunction "1_1") (pintype "passive"))
      (node (ref "R68") (pin "2") (pinfunction "2_2") (pintype "passive"))
    )
    (net (code "68") (name "Net-(R68-Pad1)") (class "Default")
      (node (ref "R68") (pin "1") (pinfunction "1_1") (pintype "passive"))
      (node (ref "R69") (pin "2") (pinfunction "2_2") (pintype "passive"))
    )
    (net (code "69") (name "Net-(R69-Pad1)") (class "Default")
      (node (ref "R69") (pin "1") (pinfunction "1_1") (pintype "passive"))
      (node (ref "R70") (pin "2") (pinfunction "2_2") (pintype "passive"))
    )
    (net (code "70") (name "Net-(R70-Pad1)") (class "Default")
      (node (ref "R70") (pin "1") (pinfunction "1_1") (pintype "passive"))
      (node (ref "R71") (pin "2") (pinfunction "2_2") (pintype "passive"))
    )
    (net (code "71") (name "Net-(R71-Pad1)") (class "Default")
      (node (ref "R71") (pin "1") (pinfunction "1_1") (pintype "passive"))
      (node (ref "R72") (pin "2") (pinfunction "2_2") (pintype "passive"))
    )
    (net (code "72") (name "Net-(R72-Pad1)") (class "Default")
      (node (ref "R72") (pin "1") (pinfunction "1_1") (pintype "passive"))
      (node (ref "R73") (pin "2") (pinfunction "2_2") (pintype "passive"))
    )
    (net (code "73") (name "Net-(R73-Pad1)") (class "Default")
      (node (ref "R73") (pin "1") (pinfunction "1_1") (pintype "passive"))
      (node (ref "R74") (pin "2") (pinfunction "2_2") (pintype "passive"))
    )
    (net (code "74") (name "Net-(R74-Pad1)") (class "Default")
      (node (ref "R74") (pin "1") (pinfunction "1_1") (pintype "passive"))
      (node (ref "R75") (pin "2") (pinfunction "2_2") (pintype "passive"))
    )
    (net (code "75") (name "Net-(R75-Pad1)") (class "Default")
      (node (ref "R75") (pin "1") (pinfunction "1_1") (pintype "passive"))
      (node (ref "R76") (pin "2") (pinfunction "2_2") (pintype "passive"))
    )
    (net (code "76") (name "Net-(R76-Pad1)") (class "Default")
      (node (ref "R76") (pin "1") (pinfunction "1_1") (pintype "passive"))
      (node (ref "R77") (pin "2") (pinfunction "2_2") (pintype "passive"))
    )
    (net (code "77") (name "Net-(R77-Pad1)") (class "Default")
      (node (ref "R77") (pin "1") (pinfunction "1_1") (pintype "passive"))
      (node (ref "R78") (pin "2") (pinfunction "2_2") (pintype "passive"))
    )
    (net (code "78") (name "Net-(R78-Pad1)") (class "Default")
      (node (ref "R78") (pin "1") (pinfunction "1_1") (pintype "passive"))
      (node (ref "R79") (pin "2") (pinfunction "2_2") (pintype "passive"))
    )
    (net (code "79") (name "Net-(R79-Pad1)") (class "Default")
      (node (ref "R79") (pin "1") (pinfunction "1_1") (pintype "passive"))
      (node (ref "R80") (pin "2") (pinfunction "2_2") (pintype "passive"))
    )
    (net (code "80") (name "Net-(R80-Pad1)") (class "Default")
      (node (ref "R80") (pin "1") (pinfunction "1_1") (pintype "passive"))
      (node (ref "R81") (pin "2") (pinfunction "2_2") (pintype "passive"))
    )
    (net (code "81") (name "Net-(R81-Pad1)") (class "Default")
      (node (ref "R81") (pin "1") (pinfunction "1_1") (pintype "passive"))
      (node (ref "R82") (pin "2") (pinfunction "2_2") (pintype "passive"))
    )
    (net (code "82") (name "Net-(R82-Pad1)") (class "Default")
      (node (ref "R82") (pin "1") (pinfunction "1_1") (pintype "passive"))
      (node (ref "R83") (pin "2") (pinfunction "2_2") (pintype "passive"))
    )
    (net (code "83") (name "Net-(R83-Pad1)") (class "Default")
      (node (ref "R83") (pin "1") (pinfunction "1_1") (pintype "passive"))
      (node (ref "R84") (pin "2") (pinfunction "2_2") (pintype "passive"))
    )
    (net (code "84") (name "Net-(R84-Pad1)") (class "Default")
      (node (ref "R84") (pin "1") (pinfunction "1_1") (pintype "passive"))
      (node (ref "R85") (pin "2") (pinfunction "2_2") (pintype "passive"))
    )
    (net (code "85") (name "Net-(R85-Pad1)") (class "Default")
      (node (ref "R85") (pin "1") (pinfunction "1_1") (pintype "passive"))
      (node (ref "R86") (pin "2") (pinfunction "2_2") (pintype "passive"))
    )
    (net (code "86") (name "Net-(R86-Pad1)") (class "Default")
      (node (ref "R86") (pin "1") (pinfunction "1_1") (pintype "passive"))
      (node (ref "R87") (pin "2") (pinfunction "2_2") (pintype "passive"))
    )
    (net (code "87") (name "Net-(R87-Pad1)") (class "Default")
      (node (ref "R87") (pin "1") (pinfunction "1_1") (pintype "passive"))
      (node (ref "R88") (pin "2") (pinfunction "2_2") (pintype "passive"))
    )
    (net (code "88") (name "Net-(R88-Pad1)") (class "Default")
      (node (ref "R88") (pin "1") (pinfunction "1_1") (pintype "passive"))
      (node (ref "R89") (pin "2") (pinfunction "2_2") (pintype "passive"))
    )
    (net (code "89") (name "Net-(R89-Pad1)") (class "Default")
      (node (ref "R89") (pin "1") (pinfunction "1_1") (pintype "passive"))
      (node (ref "R90") (pin "2") (pinfunction "2_2") (pintype "passive"))
    )
    (net (code "90") (name "Net-(R90-Pad1)") (class "Default")
      (node (ref "R90") (pin "1") (pinfunction "1_1") (pintype "passive"))
      (node (ref "R91") (pin "2") (pinfunction "2_2") (pintype "passive"))
    )
    (net (code "91") (name "Net-(R91-Pad1)") (class "Default")
      (node (ref "R91") (pin "1") (pinfunction "1_1") (pintype "passive"))
      (node (ref "R92") (pin "2") (pinfunction "2_2") (pintype "passive"))
    )
    (net (code "92") (name "Net-(R92-Pad1)") (class "Default")
      (node (ref "R92") (pin "1") (pinfunction "1_1") (pintype "passive"))
      (node (ref "R93") (pin "2") (pinfunction "2_2") (pintype "passive"))
    )
    (net (code "93") (name "Net-(R93-Pad1)") (class "Default")
      (node (ref "R93") (pin "1") (pinfunction "1_1") (pintype "passive"))
      (node (ref "R94") (pin "2") (pinfunction "2_2") (pintype "passive"))
    )
    (net (code "94") (name "Net-(R94-Pad1)") (class "Default")
      (node (ref "R94") (pin "1") (pinfunction "1_1") (pintype "passive"))
      (node (ref "R95") (pin "2") (pinfunction "2_2") (pintype "passive"))
    )
    (net (code "95") (name "Net-(R95-Pad1)") (class "Default")
      (node (ref "R95") (pin "1") (pinfunction "1_1") (pintype "passive"))
      (node (ref "R96") (pin "2") (pinfunction "2_2") (pintype "passive"))
    )
    (net (code "96") (name "Net-(R96-Pad1)") (class "Default")
      (node (ref "R96") (pin "1") (pinfunction "1_1") (pintype "passive"))
      (node (ref "R97") (pin "2") (pinfunction "2_2") (pintype "passive"))
    )
    (net (code "97") (name "Net-(R97-Pad1)") (class "Default")
      (node (ref "R97") (pin "1") (pinfunction "1_1") (pintype "passive"))
      (node (ref "R98") (pin "2") (pinfunction "2_2") (pintype "passive"))
    )
    (net (code "98") (name "Net-(R98-Pad1)") (class "Default")
      (node (ref "R98") (pin "1") (pinfunction "1_1") (pintype "passive"))
      (node (ref "R99") (pin "2") (pinfunction "2_2") (pintype "passive"))
    )
    (net (code "99") (name "Net-(R100-Pad2)") (class "Default")
      (node (ref "R100") (pin "2") (pinfunction "2_2") (pintype "passive"))
      (node (ref "R99") (pin "1") (pinfunction "1_1") (pintype "passive"))
    )
    (net (code "100") (name "Net-(TP1-TP)") (class "Default")
      (node (ref "R1") (pin "2") (pinfunction "2_2") (pintype "passive"))
      (node (ref "TP1") (pin "1") (pinfunction "TP_1") (pintype "passive"))
    )
    (net (code "101") (name "Net-(TP2-TP)") (class "Default")
      (node (ref "R100") (pin "1") (pinfunction "1_1") (pintype "passive"))
      (node (ref "TP2") (pin "1") (pinfunction "TP_1") (pintype "passive"))
    )
  )
)
